# YarnControl_motor_v1_1.net
KiCad netlist of a schematic drawn in Altium Designer
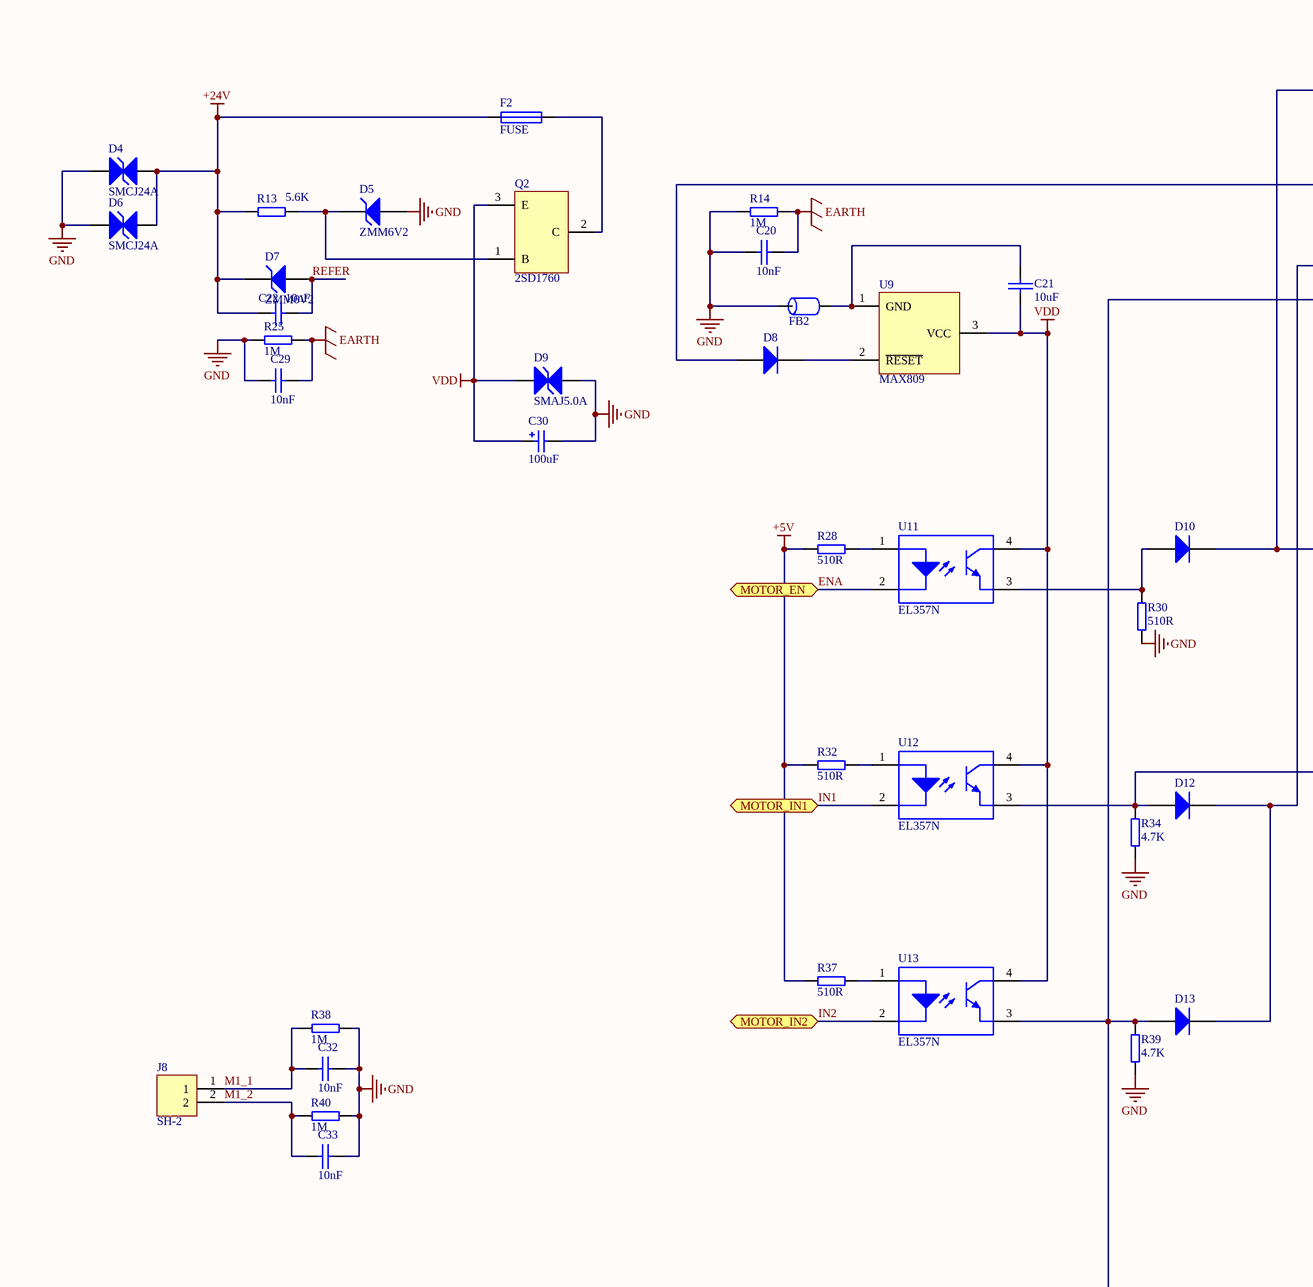
[diagram p0: YarnControl_motor_v1.1.SchDoc, left]
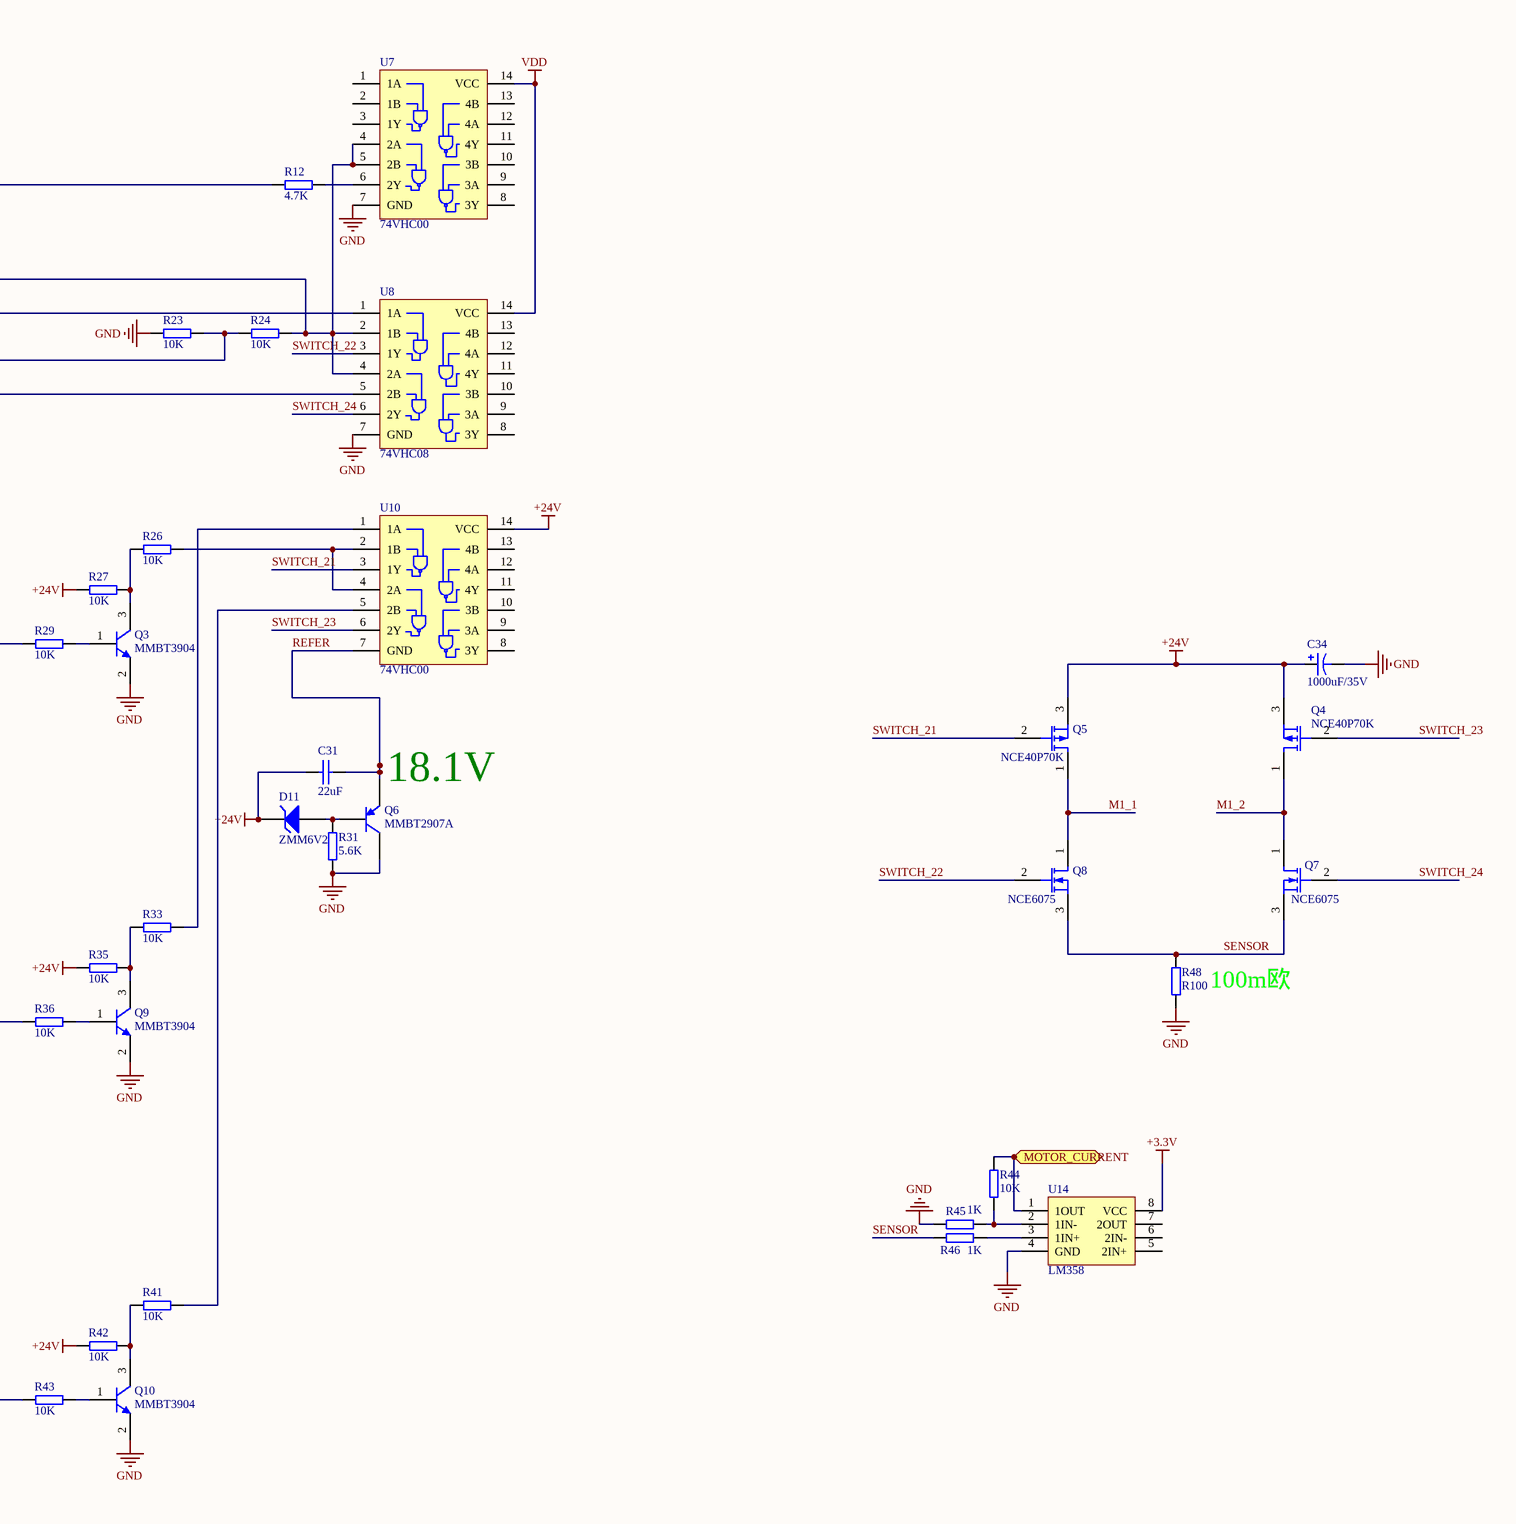
[diagram p1: YarnControl_motor_v1.1.SchDoc, right]

(export (version "E")
  (design (tool "Eeschema 10.0.6"))
  (components
    (comp (ref "C20")
      (value "10nF")
      (footprint "0805")
      (description "电容")
      (libsource (lib "Component") (part "CAP"))
    )
    (comp (ref "C21")
      (value "10uF")
      (footprint "0805")
      (description "电容")
      (libsource (lib "Component") (part "CAP"))
    )
    (comp (ref "C22")
      (value "10nF")
      (footprint "0805")
      (description "电容")
      (libsource (lib "Component") (part "CAP"))
    )
    (comp (ref "C29")
      (value "10nF")
      (footprint "0805")
      (description "电容")
      (libsource (lib "Component") (part "CAP"))
    )
    (comp (ref "C30") (value "100uF") (footprint "CA6032-C") (libsource (lib "Componet") (part "CapAEC*4")))
    (comp (ref "C31")
      (value "22uF")
      (footprint "0805")
      (description "电容")
      (libsource (lib "Component") (part "CAP"))
    )
    (comp (ref "C32")
      (value "10nF")
      (footprint "0805")
      (description "电容")
      (libsource (lib "Component") (part "CAP"))
    )
    (comp (ref "C33")
      (value "10nF")
      (footprint "0805")
      (description "电容")
      (libsource (lib "Component") (part "CAP"))
    )
    (comp (ref "C34")
      (value "1000uF/35V")
      (footprint "CAP-5mm")
      (description "Polarized Capacitor (Radial)")
      (fields (field (name "PUBLISHER") "Altium Limited"))
      (libsource (lib "Miscellaneous Devices") (part "Cap Pol1"))
    )
    (comp (ref "D4")
      (value "SMCJ24A")
      (footprint "DO-214AA/SMB")
      (fields (field (name "PUBLISHER") "Altium Limited"))
      (libsource (lib "TIAN's Schlib") (part "TVS"))
    )
    (comp (ref "D5")
      (value "ZMM6V2")
      (footprint "DIDODE_LL-34")
      (description "Zener Diode")
      (fields (field (name "PUBLISHER") "Altium Limited"))
      (libsource (lib "Miscellaneous Devices") (part "D Zener"))
    )
    (comp (ref "D6")
      (value "SMCJ24A")
      (footprint "DO-214AA/SMB")
      (fields (field (name "PUBLISHER") "Altium Limited"))
      (libsource (lib "TIAN's Schlib") (part "TVS"))
    )
    (comp (ref "D7")
      (value "ZMM6V2")
      (footprint "DIDODE_LL-34")
      (description "Zener Diode")
      (fields (field (name "PUBLISHER") "Altium Limited"))
      (libsource (lib "Miscellaneous Devices") (part "D Zener"))
    )
    (comp (ref "D8")
      (value "1N4148")
      (footprint "DIDODE_LL-34")
      (description "Default Diode")
      (fields (field (name "PUBLISHER") "Altium Limited"))
      (libsource (lib "Miscellaneous Devices") (part "Diode"))
    )
    (comp (ref "D9")
      (value "SMAJ5.0A")
      (footprint "Diode_TP2")
      (fields (field (name "PUBLISHER") "Altium Limited"))
      (libsource (lib "TIAN's Schlib") (part "TVS"))
    )
    (comp (ref "D10")
      (value "1N4148")
      (footprint "DIDODE_LL-34")
      (description "Default Diode")
      (fields (field (name "PUBLISHER") "Altium Limited"))
      (libsource (lib "Miscellaneous Devices") (part "Diode"))
    )
    (comp (ref "D11")
      (value "ZMM6V2")
      (footprint "DIDODE_LL-34")
      (description "Zener Diode")
      (fields (field (name "PUBLISHER") "Altium Limited"))
      (libsource (lib "Miscellaneous Devices") (part "D Zener"))
    )
    (comp (ref "D12")
      (value "1N4148")
      (footprint "DIDODE_LL-34")
      (description "Default Diode")
      (fields (field (name "PUBLISHER") "Altium Limited"))
      (libsource (lib "Miscellaneous Devices") (part "Diode"))
    )
    (comp (ref "D13")
      (value "1N4148")
      (footprint "DIDODE_LL-34")
      (description "Default Diode")
      (fields (field (name "PUBLISHER") "Altium Limited"))
      (libsource (lib "Miscellaneous Devices") (part "Diode"))
    )
    (comp (ref "F2")
      (value "FUSE")
      (footprint "1206")
      (description "保险丝")
      (libsource (lib "Component") (part "FUSE"))
    )
    (comp (ref "FB2") (value "FERRITE") (footprint "0805") (libsource (lib "Connector") (part "FERRITE")))
    (comp (ref "J8") (value "SH-2") (footprint "CH3.96-2P") (libsource (lib "Connector") (part "SH-2")))
    (comp (ref "Q2") (value "2SD1760") (footprint "TO-252-2L") (libsource (lib "Componet") (part "2SD1760")))
    (comp (ref "Q3") (value "MMBT3904") (footprint "SOT-23") (libsource (lib "Componet") (part "S8050")))
    (comp (ref "Q4")
      (value "NCE40P70K")
      (footprint "TO-252")
      (description "P-Channel MOSFET")
      (fields (field (name "PUBLISHER") "Altium Limited"))
      (libsource (lib "Miscellaneous Devices") (part "MOSFET-P"))
    )
    (comp (ref "Q5")
      (value "NCE40P70K")
      (footprint "TO-252")
      (description "P-Channel MOSFET")
      (fields (field (name "PUBLISHER") "Altium Limited"))
      (libsource (lib "Miscellaneous Devices") (part "MOSFET-P"))
    )
    (comp (ref "Q6") (value "MMBT2907A") (footprint "901X_SOT-23") (libsource (lib "Componet") (part "PNP")))
    (comp (ref "Q7")
      (value "NCE6075")
      (footprint "TO-252")
      (description "N-Channel MOSFET")
      (fields (field (name "PUBLISHER") "Altium Limited"))
      (libsource (lib "Miscellaneous Devices") (part "MOSFET-N"))
    )
    (comp (ref "Q8")
      (value "NCE6075")
      (footprint "TO-252")
      (description "N-Channel MOSFET")
      (fields (field (name "PUBLISHER") "Altium Limited"))
      (libsource (lib "Miscellaneous Devices") (part "MOSFET-N"))
    )
    (comp (ref "Q9") (value "MMBT3904") (footprint "SOT-23") (libsource (lib "Componet") (part "S8050")))
    (comp (ref "Q10") (value "MMBT3904") (footprint "SOT-23") (libsource (lib "Componet") (part "S8050")))
    (comp (ref "R12")
      (value "4.7K")
      (footprint "0805")
      (description "电阻")
      (libsource (lib "Component") (part "RES"))
    )
    (comp (ref "R13")
      (value "5.6K")
      (footprint "0805")
      (description "电阻")
      (libsource (lib "Component") (part "RES"))
    )
    (comp (ref "R14")
      (value "1M")
      (footprint "0805")
      (description "电阻")
      (libsource (lib "Component") (part "RES"))
    )
    (comp (ref "R23")
      (value "10K")
      (footprint "0805")
      (description "电阻")
      (libsource (lib "Component") (part "RES"))
    )
    (comp (ref "R24")
      (value "10K")
      (footprint "0805")
      (description "电阻")
      (libsource (lib "Component") (part "RES"))
    )
    (comp (ref "R25")
      (value "1M")
      (footprint "0805")
      (description "电阻")
      (libsource (lib "Component") (part "RES"))
    )
    (comp (ref "R26")
      (value "10K")
      (footprint "0805")
      (description "电阻")
      (libsource (lib "Component") (part "RES"))
    )
    (comp (ref "R27")
      (value "10K")
      (footprint "0805")
      (description "电阻")
      (libsource (lib "Component") (part "RES"))
    )
    (comp (ref "R28")
      (value "510R")
      (footprint "0805")
      (description "电阻")
      (libsource (lib "Component") (part "RES"))
    )
    (comp (ref "R29")
      (value "10K")
      (footprint "0805")
      (description "电阻")
      (libsource (lib "Component") (part "RES"))
    )
    (comp (ref "R30")
      (value "510R")
      (footprint "0805")
      (description "电阻")
      (libsource (lib "Component") (part "RES"))
    )
    (comp (ref "R31")
      (value "5.6K")
      (footprint "0805")
      (description "电阻")
      (libsource (lib "Component") (part "RES"))
    )
    (comp (ref "R32")
      (value "510R")
      (footprint "0805")
      (description "电阻")
      (libsource (lib "Component") (part "RES"))
    )
    (comp (ref "R33")
      (value "10K")
      (footprint "0805")
      (description "电阻")
      (libsource (lib "Component") (part "RES"))
    )
    (comp (ref "R34")
      (value "4.7K")
      (footprint "0805")
      (description "电阻")
      (libsource (lib "Component") (part "RES"))
    )
    (comp (ref "R35")
      (value "10K")
      (footprint "0805")
      (description "电阻")
      (libsource (lib "Component") (part "RES"))
    )
    (comp (ref "R36")
      (value "10K")
      (footprint "0805")
      (description "电阻")
      (libsource (lib "Component") (part "RES"))
    )
    (comp (ref "R37")
      (value "510R")
      (footprint "0805")
      (description "电阻")
      (libsource (lib "Component") (part "RES"))
    )
    (comp (ref "R38")
      (value "1M")
      (footprint "0805")
      (description "电阻")
      (libsource (lib "Component") (part "RES"))
    )
    (comp (ref "R39")
      (value "4.7K")
      (footprint "0805")
      (description "电阻")
      (libsource (lib "Component") (part "RES"))
    )
    (comp (ref "R40")
      (value "1M")
      (footprint "0805")
      (description "电阻")
      (libsource (lib "Component") (part "RES"))
    )
    (comp (ref "R41")
      (value "10K")
      (footprint "0805")
      (description "电阻")
      (libsource (lib "Component") (part "RES"))
    )
    (comp (ref "R42")
      (value "10K")
      (footprint "0805")
      (description "电阻")
      (libsource (lib "Component") (part "RES"))
    )
    (comp (ref "R43")
      (value "10K")
      (footprint "0805")
      (description "电阻")
      (libsource (lib "Component") (part "RES"))
    )
    (comp (ref "R44")
      (value "10K")
      (footprint "0805")
      (description "电阻")
      (libsource (lib "Component") (part "RES"))
    )
    (comp (ref "R45")
      (value "1K")
      (footprint "0805")
      (description "电阻")
      (libsource (lib "Component") (part "RES"))
    )
    (comp (ref "R46")
      (value "1K")
      (footprint "0805")
      (description "电阻")
      (libsource (lib "Component") (part "RES"))
    )
    (comp (ref "R48")
      (value "R100")
      (footprint "2512")
      (description "电阻")
      (libsource (lib "Component") (part "RES"))
    )
    (comp (ref "U7") (value "74VHC00") (footprint "SO-14") (libsource (lib "Chip") (part "74VHC00")))
    (comp (ref "U8") (value "74VHC08") (footprint "SO-14") (libsource (lib "Chip") (part "74HC08")))
    (comp (ref "U9") (value "MAX809") (footprint "SOT-23") (libsource (lib "Chip") (part "MAX809")))
    (comp (ref "U10") (value "74VHC00") (footprint "SO-14") (libsource (lib "Chip") (part "74VHC00")))
    (comp (ref "U11") (value "EL357N") (footprint "EL357N") (libsource (lib "Componet") (part "EL357N")))
    (comp (ref "U12") (value "EL357N") (footprint "EL357N") (libsource (lib "Componet") (part "EL357N")))
    (comp (ref "U13") (value "EL357N") (footprint "EL357N") (libsource (lib "Componet") (part "EL357N")))
    (comp (ref "U14") (value "LM358") (footprint "SO-8") (libsource (lib "Chip") (part "LM358")))
  )
  (nets
    (net (code "1") (name "+3.3V") (class "Default")
      (node (ref "U14") (pin "8") (pinfunction "VCC_8") (pintype "passive"))
    )
    (net (code "2") (name "+5V") (class "Default")
      (node (ref "R28") (pin "1") (pinfunction "1_1") (pintype "passive"))
      (node (ref "R32") (pin "1") (pinfunction "1_1") (pintype "passive"))
      (node (ref "R37") (pin "1") (pinfunction "1_1") (pintype "passive"))
    )
    (net (code "3") (name "+24V") (class "Default")
      (node (ref "C22") (pin "1") (pinfunction "1_1") (pintype "passive"))
      (node (ref "C31") (pin "2") (pinfunction "2_2") (pintype "passive"))
      (node (ref "C34") (pin "1") (pinfunction "1_1") (pintype "passive"))
      (node (ref "D11") (pin "2") (pinfunction "K_2") (pintype "passive"))
      (node (ref "D4") (pin "1") (pinfunction "A_1") (pintype "passive"))
      (node (ref "D6") (pin "1") (pinfunction "A_1") (pintype "passive"))
      (node (ref "D7") (pin "2") (pinfunction "K_2") (pintype "passive"))
      (node (ref "F2") (pin "2") (pinfunction "2_2") (pintype "passive"))
      (node (ref "Q4") (pin "3") (pinfunction "S_3") (pintype "passive"))
      (node (ref "Q5") (pin "3") (pinfunction "S_3") (pintype "passive"))
      (node (ref "R13") (pin "1") (pinfunction "1_1") (pintype "passive"))
      (node (ref "R27") (pin "1") (pinfunction "1_1") (pintype "passive"))
      (node (ref "R35") (pin "1") (pinfunction "1_1") (pintype "passive"))
      (node (ref "R42") (pin "1") (pinfunction "1_1") (pintype "passive"))
      (node (ref "U10") (pin "14") (pinfunction "VCC_14") (pintype "passive"))
    )
    (net (code "4") (name "/ENA") (class "Default")
      (node (ref "U11") (pin "2") (pinfunction "Vin-_2") (pintype "passive"))
    )
    (net (code "5") (name "/IN1") (class "Default")
      (node (ref "U12") (pin "2") (pinfunction "Vin-_2") (pintype "passive"))
    )
    (net (code "6") (name "/IN2") (class "Default")
      (node (ref "U13") (pin "2") (pinfunction "Vin-_2") (pintype "passive"))
    )
    (net (code "7") (name "/M1_1") (class "Default")
      (node (ref "C32") (pin "2") (pinfunction "2_2") (pintype "passive"))
      (node (ref "J8") (pin "1") (pinfunction "1_1") (pintype "passive"))
      (node (ref "Q5") (pin "1") (pinfunction "D_1") (pintype "passive"))
      (node (ref "Q8") (pin "1") (pinfunction "D_1") (pintype "passive"))
      (node (ref "R38") (pin "1") (pinfunction "1_1") (pintype "passive"))
    )
    (net (code "8") (name "/M1_2") (class "Default")
      (node (ref "C33") (pin "2") (pinfunction "2_2") (pintype "passive"))
      (node (ref "J8") (pin "2") (pinfunction "2_2") (pintype "passive"))
      (node (ref "Q4") (pin "1") (pinfunction "D_1") (pintype "passive"))
      (node (ref "Q7") (pin "1") (pinfunction "D_1") (pintype "passive"))
      (node (ref "R40") (pin "1") (pinfunction "1_1") (pintype "passive"))
    )
    (net (code "9") (name "/MOTOR_CURRENT") (class "Default")
      (node (ref "R44") (pin "1") (pinfunction "1_1") (pintype "passive"))
      (node (ref "U14") (pin "1") (pinfunction "1OUT_1") (pintype "passive"))
    )
    (net (code "10") (name "/REFER") (class "Default")
      (node (ref "C22") (pin "2") (pinfunction "2_2") (pintype "passive"))
      (node (ref "C31") (pin "1") (pinfunction "1_1") (pintype "passive"))
      (node (ref "D7") (pin "1") (pinfunction "A_1") (pintype "passive"))
      (node (ref "Q6") (pin "3") (pinfunction "E_3") (pintype "passive"))
      (node (ref "U10") (pin "7") (pinfunction "GND_7") (pintype "passive"))
    )
    (net (code "11") (name "/SENSOR") (class "Default")
      (node (ref "Q7") (pin "3") (pinfunction "S_3") (pintype "passive"))
      (node (ref "Q8") (pin "3") (pinfunction "S_3") (pintype "passive"))
      (node (ref "R46") (pin "2") (pinfunction "2_2") (pintype "passive"))
      (node (ref "R48") (pin "2") (pinfunction "2_2") (pintype "passive"))
    )
    (net (code "12") (name "/SWITCH_21") (class "Default")
      (node (ref "Q5") (pin "2") (pinfunction "G_2") (pintype "passive"))
      (node (ref "U10") (pin "3") (pinfunction "1Y_3") (pintype "passive"))
    )
    (net (code "13") (name "/SWITCH_22") (class "Default")
      (node (ref "Q8") (pin "2") (pinfunction "G_2") (pintype "passive"))
      (node (ref "U8") (pin "3") (pinfunction "1Y_3") (pintype "passive"))
    )
    (net (code "14") (name "/SWITCH_23") (class "Default")
      (node (ref "Q4") (pin "2") (pinfunction "G_2") (pintype "passive"))
      (node (ref "U10") (pin "6") (pinfunction "2Y_6") (pintype "passive"))
    )
    (net (code "15") (name "/SWITCH_24") (class "Default")
      (node (ref "Q7") (pin "2") (pinfunction "G_2") (pintype "passive"))
      (node (ref "U8") (pin "6") (pinfunction "2Y_6") (pintype "passive"))
    )
    (net (code "16") (name "EARTH") (class "Default")
      (node (ref "C20") (pin "1") (pinfunction "1_1") (pintype "passive"))
      (node (ref "C29") (pin "1") (pinfunction "1_1") (pintype "passive"))
      (node (ref "R14") (pin "2") (pinfunction "2_2") (pintype "passive"))
      (node (ref "R25") (pin "2") (pinfunction "2_2") (pintype "passive"))
    )
    (net (code "17") (name "GND") (class "Default")
      (node (ref "C20") (pin "2") (pinfunction "2_2") (pintype "passive"))
      (node (ref "C29") (pin "2") (pinfunction "2_2") (pintype "passive"))
      (node (ref "C30") (pin "2") (pinfunction "2_2") (pintype "passive"))
      (node (ref "C32") (pin "1") (pinfunction "1_1") (pintype "passive"))
      (node (ref "C33") (pin "1") (pinfunction "1_1") (pintype "passive"))
      (node (ref "C34") (pin "2") (pinfunction "2_2") (pintype "passive"))
      (node (ref "D4") (pin "2") (pinfunction "K_2") (pintype "passive"))
      (node (ref "D5") (pin "1") (pinfunction "A_1") (pintype "passive"))
      (node (ref "D6") (pin "2") (pinfunction "K_2") (pintype "passive"))
      (node (ref "D9") (pin "1") (pinfunction "A_1") (pintype "passive"))
      (node (ref "FB2") (pin "2") (pinfunction "2_2") (pintype "passive"))
      (node (ref "Q10") (pin "2") (pinfunction "E_2") (pintype "passive"))
      (node (ref "Q3") (pin "2") (pinfunction "E_2") (pintype "passive"))
      (node (ref "Q6") (pin "1") (pinfunction "C_1") (pintype "passive"))
      (node (ref "Q9") (pin "2") (pinfunction "E_2") (pintype "passive"))
      (node (ref "R14") (pin "1") (pinfunction "1_1") (pintype "passive"))
      (node (ref "R23") (pin "1") (pinfunction "1_1") (pintype "passive"))
      (node (ref "R25") (pin "1") (pinfunction "1_1") (pintype "passive"))
      (node (ref "R30") (pin "1") (pinfunction "1_1") (pintype "passive"))
      (node (ref "R31") (pin "1") (pinfunction "1_1") (pintype "passive"))
      (node (ref "R34") (pin "1") (pinfunction "1_1") (pintype "passive"))
      (node (ref "R38") (pin "2") (pinfunction "2_2") (pintype "passive"))
      (node (ref "R39") (pin "1") (pinfunction "1_1") (pintype "passive"))
      (node (ref "R40") (pin "2") (pinfunction "2_2") (pintype "passive"))
      (node (ref "R45") (pin "2") (pinfunction "2_2") (pintype "passive"))
      (node (ref "R48") (pin "1") (pinfunction "1_1") (pintype "passive"))
      (node (ref "U14") (pin "4") (pinfunction "GND_4") (pintype "passive"))
      (node (ref "U7") (pin "7") (pinfunction "GND_7") (pintype "passive"))
      (node (ref "U8") (pin "7") (pinfunction "GND_7") (pintype "passive"))
    )
    (net (code "18") (name "Net-(D5-K)") (class "Default")
      (node (ref "D5") (pin "2") (pinfunction "K_2") (pintype "passive"))
      (node (ref "Q2") (pin "1") (pinfunction "B_1") (pintype "passive"))
      (node (ref "R13") (pin "2") (pinfunction "2_2") (pintype "passive"))
    )
    (net (code "19") (name "Net-(D8-A)") (class "Default")
      (node (ref "D8") (pin "1") (pinfunction "A_1") (pintype "passive"))
      (node (ref "R24") (pin "2") (pinfunction "2_2") (pintype "passive"))
      (node (ref "U7") (pin "4") (pinfunction "2A_4") (pintype "passive"))
      (node (ref "U7") (pin "5") (pinfunction "2B_5") (pintype "passive"))
      (node (ref "U8") (pin "2") (pinfunction "1B_2") (pintype "passive"))
      (node (ref "U8") (pin "4") (pinfunction "2A_4") (pintype "passive"))
    )
    (net (code "20") (name "Net-(D8-K)") (class "Default")
      (node (ref "D8") (pin "2") (pinfunction "K_2") (pintype "passive"))
      (node (ref "U9") (pin "2") (pinfunction "~{RESET}_2") (pintype "passive"))
    )
    (net (code "21") (name "Net-(D10-A)") (class "Default")
      (node (ref "D10") (pin "1") (pinfunction "A_1") (pintype "passive"))
      (node (ref "R30") (pin "2") (pinfunction "2_2") (pintype "passive"))
      (node (ref "U11") (pin "3") (pinfunction "E_3") (pintype "passive"))
    )
    (net (code "22") (name "Net-(D10-K)") (class "Default")
      (node (ref "D10") (pin "2") (pinfunction "K_2") (pintype "passive"))
      (node (ref "R12") (pin "1") (pinfunction "1_1") (pintype "passive"))
      (node (ref "R29") (pin "1") (pinfunction "1_1") (pintype "passive"))
    )
    (net (code "23") (name "Net-(D11-A)") (class "Default")
      (node (ref "D11") (pin "1") (pinfunction "A_1") (pintype "passive"))
      (node (ref "Q6") (pin "2") (pinfunction "B_2") (pintype "passive"))
      (node (ref "R31") (pin "2") (pinfunction "2_2") (pintype "passive"))
    )
    (net (code "24") (name "Net-(D12-A)") (class "Default")
      (node (ref "D12") (pin "1") (pinfunction "A_1") (pintype "passive"))
      (node (ref "R34") (pin "2") (pinfunction "2_2") (pintype "passive"))
      (node (ref "R36") (pin "1") (pinfunction "1_1") (pintype "passive"))
      (node (ref "U12") (pin "3") (pinfunction "E_3") (pintype "passive"))
      (node (ref "U8") (pin "1") (pinfunction "1A_1") (pintype "passive"))
    )
    (net (code "25") (name "Net-(D12-K)") (class "Default")
      (node (ref "D12") (pin "2") (pinfunction "K_2") (pintype "passive"))
      (node (ref "D13") (pin "2") (pinfunction "K_2") (pintype "passive"))
      (node (ref "R23") (pin "2") (pinfunction "2_2") (pintype "passive"))
      (node (ref "R24") (pin "1") (pinfunction "1_1") (pintype "passive"))
    )
    (net (code "26") (name "Net-(D13-A)") (class "Default")
      (node (ref "D13") (pin "1") (pinfunction "A_1") (pintype "passive"))
      (node (ref "R39") (pin "2") (pinfunction "2_2") (pintype "passive"))
      (node (ref "R43") (pin "1") (pinfunction "1_1") (pintype "passive"))
      (node (ref "U13") (pin "3") (pinfunction "E_3") (pintype "passive"))
      (node (ref "U8") (pin "5") (pinfunction "2B_5") (pintype "passive"))
    )
    (net (code "27") (name "Net-(Q2-C)") (class "Default")
      (node (ref "F2") (pin "1") (pinfunction "1_1") (pintype "passive"))
      (node (ref "Q2") (pin "2") (pinfunction "C_2") (pintype "passive"))
    )
    (net (code "28") (name "Net-(Q3-B)") (class "Default")
      (node (ref "Q3") (pin "1") (pinfunction "B_1") (pintype "passive"))
      (node (ref "R29") (pin "2") (pinfunction "2_2") (pintype "passive"))
    )
    (net (code "29") (name "Net-(Q3-C)") (class "Default")
      (node (ref "Q3") (pin "3") (pinfunction "C_3") (pintype "passive"))
      (node (ref "R26") (pin "1") (pinfunction "1_1") (pintype "passive"))
      (node (ref "R27") (pin "2") (pinfunction "2_2") (pintype "passive"))
    )
    (net (code "30") (name "Net-(Q9-B)") (class "Default")
      (node (ref "Q9") (pin "1") (pinfunction "B_1") (pintype "passive"))
      (node (ref "R36") (pin "2") (pinfunction "2_2") (pintype "passive"))
    )
    (net (code "31") (name "Net-(Q9-C)") (class "Default")
      (node (ref "Q9") (pin "3") (pinfunction "C_3") (pintype "passive"))
      (node (ref "R33") (pin "1") (pinfunction "1_1") (pintype "passive"))
      (node (ref "R35") (pin "2") (pinfunction "2_2") (pintype "passive"))
    )
    (net (code "32") (name "Net-(Q10-B)") (class "Default")
      (node (ref "Q10") (pin "1") (pinfunction "B_1") (pintype "passive"))
      (node (ref "R43") (pin "2") (pinfunction "2_2") (pintype "passive"))
    )
    (net (code "33") (name "Net-(Q10-C)") (class "Default")
      (node (ref "Q10") (pin "3") (pinfunction "C_3") (pintype "passive"))
      (node (ref "R41") (pin "1") (pinfunction "1_1") (pintype "passive"))
      (node (ref "R42") (pin "2") (pinfunction "2_2") (pintype "passive"))
    )
    (net (code "34") (name "Net-(U7-2Y)") (class "Default")
      (node (ref "R12") (pin "2") (pinfunction "2_2") (pintype "passive"))
      (node (ref "U7") (pin "6") (pinfunction "2Y_6") (pintype "passive"))
    )
    (net (code "35") (name "Net-(U9-GND)") (class "Default")
      (node (ref "C21") (pin "2") (pinfunction "2_2") (pintype "passive"))
      (node (ref "FB2") (pin "1") (pinfunction "1_1") (pintype "passive"))
      (node (ref "U9") (pin "1") (pinfunction "GND_1") (pintype "passive"))
    )
    (net (code "36") (name "Net-(U10-1A)") (class "Default")
      (node (ref "R33") (pin "2") (pinfunction "2_2") (pintype "passive"))
      (node (ref "U10") (pin "1") (pinfunction "1A_1") (pintype "passive"))
    )
    (net (code "37") (name "Net-(U10-1B)") (class "Default")
      (node (ref "R26") (pin "2") (pinfunction "2_2") (pintype "passive"))
      (node (ref "U10") (pin "2") (pinfunction "1B_2") (pintype "passive"))
      (node (ref "U10") (pin "4") (pinfunction "2A_4") (pintype "passive"))
    )
    (net (code "38") (name "Net-(U10-2B)") (class "Default")
      (node (ref "R41") (pin "2") (pinfunction "2_2") (pintype "passive"))
      (node (ref "U10") (pin "5") (pinfunction "2B_5") (pintype "passive"))
    )
    (net (code "39") (name "Net-(U11-Vin+)") (class "Default")
      (node (ref "R28") (pin "2") (pinfunction "2_2") (pintype "passive"))
      (node (ref "U11") (pin "1") (pinfunction "Vin+_1") (pintype "passive"))
    )
    (net (code "40") (name "Net-(U12-Vin+)") (class "Default")
      (node (ref "R32") (pin "2") (pinfunction "2_2") (pintype "passive"))
      (node (ref "U12") (pin "1") (pinfunction "Vin+_1") (pintype "passive"))
    )
    (net (code "41") (name "Net-(U13-Vin+)") (class "Default")
      (node (ref "R37") (pin "2") (pinfunction "2_2") (pintype "passive"))
      (node (ref "U13") (pin "1") (pinfunction "Vin+_1") (pintype "passive"))
    )
    (net (code "42") (name "Net-(U14-1IN+)") (class "Default")
      (node (ref "R46") (pin "1") (pinfunction "1_1") (pintype "passive"))
      (node (ref "U14") (pin "3") (pinfunction "1IN+_3") (pintype "passive"))
    )
    (net (code "43") (name "Net-(U14-1IN-)") (class "Default")
      (node (ref "R44") (pin "2") (pinfunction "2_2") (pintype "passive"))
      (node (ref "R45") (pin "1") (pinfunction "1_1") (pintype "passive"))
      (node (ref "U14") (pin "2") (pinfunction "1IN-_2") (pintype "passive"))
    )
    (net (code "44") (name "VDD") (class "Default")
      (node (ref "C21") (pin "1") (pinfunction "1_1") (pintype "passive"))
      (node (ref "C30") (pin "1") (pinfunction "1_1") (pintype "passive"))
      (node (ref "D9") (pin "2") (pinfunction "K_2") (pintype "passive"))
      (node (ref "Q2") (pin "3") (pinfunction "E_3") (pintype "passive"))
      (node (ref "U11") (pin "4") (pinfunction "C_4") (pintype "passive"))
      (node (ref "U12") (pin "4") (pinfunction "C_4") (pintype "passive"))
      (node (ref "U13") (pin "4") (pinfunction "C_4") (pintype "passive"))
      (node (ref "U7") (pin "14") (pinfunction "VCC_14") (pintype "passive"))
      (node (ref "U8") (pin "14") (pinfunction "VCC_14") (pintype "passive"))
      (node (ref "U9") (pin "3") (pinfunction "VCC_3") (pintype "passive"))
    )
    (net (code "45") (name "unconnected-(U7-1A-Pad1)") (class "Default")
      (node (ref "U7") (pin "1") (pinfunction "1A_1") (pintype "passive"))
    )
    (net (code "46") (name "unconnected-(U7-1B-Pad2)") (class "Default")
      (node (ref "U7") (pin "2") (pinfunction "1B_2") (pintype "passive"))
    )
    (net (code "47") (name "unconnected-(U7-1Y-Pad3)") (class "Default")
      (node (ref "U7") (pin "3") (pinfunction "1Y_3") (pintype "passive"))
    )
    (net (code "48") (name "unconnected-(U7-3A-Pad9)") (class "Default")
      (node (ref "U7") (pin "9") (pinfunction "3A_9") (pintype "passive"))
    )
    (net (code "49") (name "unconnected-(U7-3B-Pad10)") (class "Default")
      (node (ref "U7") (pin "10") (pinfunction "3B_10") (pintype "passive"))
    )
    (net (code "50") (name "unconnected-(U7-3Y-Pad8)") (class "Default")
      (node (ref "U7") (pin "8") (pinfunction "3Y_8") (pintype "passive"))
    )
    (net (code "51") (name "unconnected-(U7-4A-Pad12)") (class "Default")
      (node (ref "U7") (pin "12") (pinfunction "4A_12") (pintype "passive"))
    )
    (net (code "52") (name "unconnected-(U7-4B-Pad13)") (class "Default")
      (node (ref "U7") (pin "13") (pinfunction "4B_13") (pintype "passive"))
    )
    (net (code "53") (name "unconnected-(U7-4Y-Pad11)") (class "Default")
      (node (ref "U7") (pin "11") (pinfunction "4Y_11") (pintype "passive"))
    )
    (net (code "54") (name "unconnected-(U8-3A-Pad9)") (class "Default")
      (node (ref "U8") (pin "9") (pinfunction "3A_9") (pintype "passive"))
    )
    (net (code "55") (name "unconnected-(U8-3B-Pad10)") (class "Default")
      (node (ref "U8") (pin "10") (pinfunction "3B_10") (pintype "passive"))
    )
    (net (code "56") (name "unconnected-(U8-3Y-Pad8)") (class "Default")
      (node (ref "U8") (pin "8") (pinfunction "3Y_8") (pintype "passive"))
    )
    (net (code "57") (name "unconnected-(U8-4A-Pad12)") (class "Default")
      (node (ref "U8") (pin "12") (pinfunction "4A_12") (pintype "passive"))
    )
    (net (code "58") (name "unconnected-(U8-4B-Pad13)") (class "Default")
      (node (ref "U8") (pin "13") (pinfunction "4B_13") (pintype "passive"))
    )
    (net (code "59") (name "unconnected-(U8-4Y-Pad11)") (class "Default")
      (node (ref "U8") (pin "11") (pinfunction "4Y_11") (pintype "passive"))
    )
    (net (code "60") (name "unconnected-(U10-3A-Pad9)") (class "Default")
      (node (ref "U10") (pin "9") (pinfunction "3A_9") (pintype "passive"))
    )
    (net (code "61") (name "unconnected-(U10-3B-Pad10)") (class "Default")
      (node (ref "U10") (pin "10") (pinfunction "3B_10") (pintype "passive"))
    )
    (net (code "62") (name "unconnected-(U10-3Y-Pad8)") (class "Default")
      (node (ref "U10") (pin "8") (pinfunction "3Y_8") (pintype "passive"))
    )
    (net (code "63") (name "unconnected-(U10-4A-Pad12)") (class "Default")
      (node (ref "U10") (pin "12") (pinfunction "4A_12") (pintype "passive"))
    )
    (net (code "64") (name "unconnected-(U10-4B-Pad13)") (class "Default")
      (node (ref "U10") (pin "13") (pinfunction "4B_13") (pintype "passive"))
    )
    (net (code "65") (name "unconnected-(U10-4Y-Pad11)") (class "Default")
      (node (ref "U10") (pin "11") (pinfunction "4Y_11") (pintype "passive"))
    )
    (net (code "66") (name "unconnected-(U14-2IN+-Pad5)") (class "Default")
      (node (ref "U14") (pin "5") (pinfunction "2IN+_5") (pintype "passive"))
    )
    (net (code "67") (name "unconnected-(U14-2IN--Pad6)") (class "Default")
      (node (ref "U14") (pin "6") (pinfunction "2IN-_6") (pintype "passive"))
    )
    (net (code "68") (name "unconnected-(U14-2OUT-Pad7)") (class "Default")
      (node (ref "U14") (pin "7") (pinfunction "2OUT_7") (pintype "passive"))
    )
  )
)
